# LEDs.net
KiCad netlist of a schematic drawn in Altium Designer
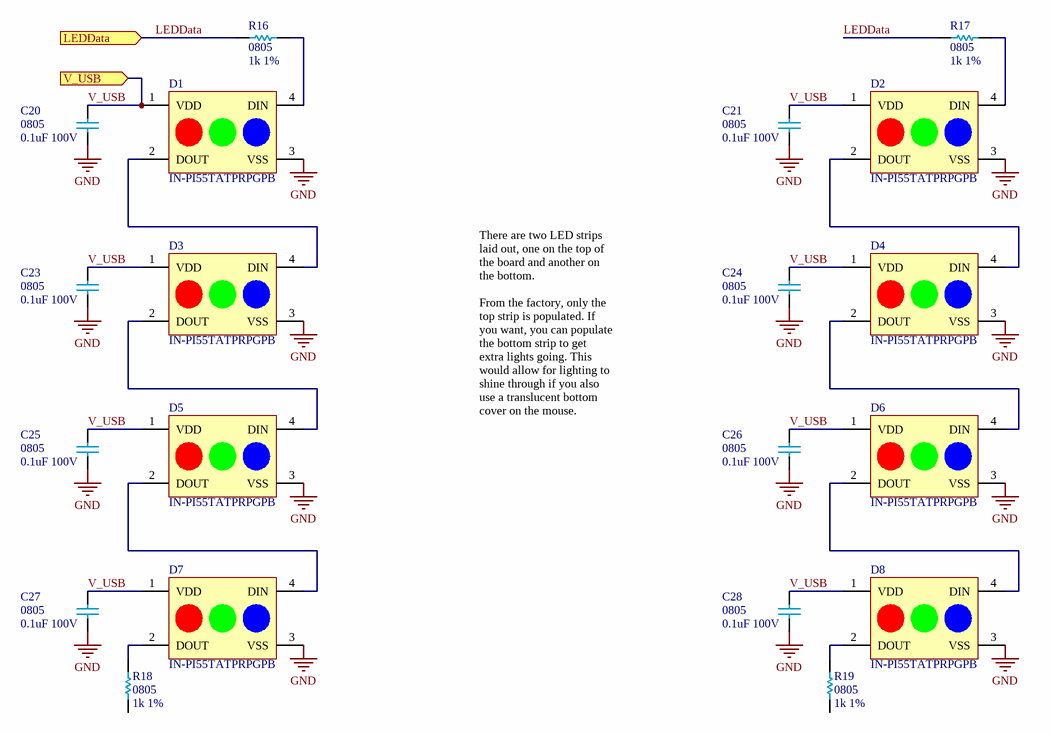
[diagram p0: LEDs.SchDoc]

(export (version "E")
  (design (tool "Eeschema 10.0.6"))
  (components
    (comp (ref "C20")
      (value "0805")
      (footprint "0805")
      (description "0805, X5R or better")
      (fields (field (name "ALTIUM_VALUE") "0.1uF 100V"))
      (libsource (lib "Chip_Passives") (part "Cap 0.1uF 100V"))
    )
    (comp (ref "C21")
      (value "0805")
      (footprint "0805")
      (description "0805, X5R or better")
      (fields (field (name "ALTIUM_VALUE") "0.1uF 100V"))
      (libsource (lib "Chip_Passives") (part "Cap 0.1uF 100V"))
    )
    (comp (ref "C23")
      (value "0805")
      (footprint "0805")
      (description "0805, X5R or better")
      (fields (field (name "ALTIUM_VALUE") "0.1uF 100V"))
      (libsource (lib "Chip_Passives") (part "Cap 0.1uF 100V"))
    )
    (comp (ref "C24")
      (value "0805")
      (footprint "0805")
      (description "0805, X5R or better")
      (fields (field (name "ALTIUM_VALUE") "0.1uF 100V"))
      (libsource (lib "Chip_Passives") (part "Cap 0.1uF 100V"))
    )
    (comp (ref "C25")
      (value "0805")
      (footprint "0805")
      (description "0805, X5R or better")
      (fields (field (name "ALTIUM_VALUE") "0.1uF 100V"))
      (libsource (lib "Chip_Passives") (part "Cap 0.1uF 100V"))
    )
    (comp (ref "C26")
      (value "0805")
      (footprint "0805")
      (description "0805, X5R or better")
      (fields (field (name "ALTIUM_VALUE") "0.1uF 100V"))
      (libsource (lib "Chip_Passives") (part "Cap 0.1uF 100V"))
    )
    (comp (ref "C27")
      (value "0805")
      (footprint "0805")
      (description "0805, X5R or better")
      (fields (field (name "ALTIUM_VALUE") "0.1uF 100V"))
      (libsource (lib "Chip_Passives") (part "Cap 0.1uF 100V"))
    )
    (comp (ref "C28")
      (value "0805")
      (footprint "0805")
      (description "0805, X5R or better")
      (fields (field (name "ALTIUM_VALUE") "0.1uF 100V"))
      (libsource (lib "Chip_Passives") (part "Cap 0.1uF 100V"))
    )
    (comp (ref "D1")
      (value "IN-PI55TATPRPGPB")
      (footprint "IN-PI55TATPRPGPB")
      (description "ADDRESS LED DISCRETE SERIAL RGB")
      (libsource (lib "LEDs") (part "IN-PI55TATPRPGPB"))
    )
    (comp (ref "D2")
      (value "IN-PI55TATPRPGPB")
      (footprint "IN-PI55TATPRPGPB")
      (description "ADDRESS LED DISCRETE SERIAL RGB")
      (libsource (lib "LEDs") (part "IN-PI55TATPRPGPB"))
    )
    (comp (ref "D3")
      (value "IN-PI55TATPRPGPB")
      (footprint "IN-PI55TATPRPGPB")
      (description "ADDRESS LED DISCRETE SERIAL RGB")
      (libsource (lib "LEDs") (part "IN-PI55TATPRPGPB"))
    )
    (comp (ref "D4")
      (value "IN-PI55TATPRPGPB")
      (footprint "IN-PI55TATPRPGPB")
      (description "ADDRESS LED DISCRETE SERIAL RGB")
      (libsource (lib "LEDs") (part "IN-PI55TATPRPGPB"))
    )
    (comp (ref "D5")
      (value "IN-PI55TATPRPGPB")
      (footprint "IN-PI55TATPRPGPB")
      (description "ADDRESS LED DISCRETE SERIAL RGB")
      (libsource (lib "LEDs") (part "IN-PI55TATPRPGPB"))
    )
    (comp (ref "D6")
      (value "IN-PI55TATPRPGPB")
      (footprint "IN-PI55TATPRPGPB")
      (description "ADDRESS LED DISCRETE SERIAL RGB")
      (libsource (lib "LEDs") (part "IN-PI55TATPRPGPB"))
    )
    (comp (ref "D7")
      (value "IN-PI55TATPRPGPB")
      (footprint "IN-PI55TATPRPGPB")
      (description "ADDRESS LED DISCRETE SERIAL RGB")
      (libsource (lib "LEDs") (part "IN-PI55TATPRPGPB"))
    )
    (comp (ref "D8")
      (value "IN-PI55TATPRPGPB")
      (footprint "IN-PI55TATPRPGPB")
      (description "ADDRESS LED DISCRETE SERIAL RGB")
      (libsource (lib "LEDs") (part "IN-PI55TATPRPGPB"))
    )
    (comp (ref "R16")
      (value "0805")
      (footprint "0805")
      (description "Chip resistor, 1/8W 100PPM")
      (fields (field (name "ALTIUM_VALUE") "1k 1%"))
      (libsource (lib "Chip_Passives") (part "Res 1k 1% 0805"))
    )
    (comp (ref "R17")
      (value "0805")
      (footprint "0805")
      (description "Chip resistor, 1/8W 100PPM")
      (fields (field (name "ALTIUM_VALUE") "1k 1%"))
      (libsource (lib "Chip_Passives") (part "Res 1k 1% 0805"))
    )
    (comp (ref "R18")
      (value "0805")
      (footprint "0805")
      (description "Chip resistor, 1/8W 100PPM")
      (fields (field (name "ALTIUM_VALUE") "1k 1%"))
      (libsource (lib "Chip_Passives") (part "Res 1k 1% 0805"))
    )
    (comp (ref "R19")
      (value "0805")
      (footprint "0805")
      (description "Chip resistor, 1/8W 100PPM")
      (fields (field (name "ALTIUM_VALUE") "1k 1%"))
      (libsource (lib "Chip_Passives") (part "Res 1k 1% 0805"))
    )
  )
  (nets
    (net (code "1") (name "/LEDData") (class "Default")
      (node (ref "R16") (pin "2") (pinfunction "2_2") (pintype "passive"))
      (node (ref "R17") (pin "2") (pinfunction "2_2") (pintype "passive"))
    )
    (net (code "2") (name "/V_USB") (class "Default")
      (node (ref "C20") (pin "2") (pinfunction "2_2") (pintype "passive"))
      (node (ref "C21") (pin "2") (pinfunction "2_2") (pintype "passive"))
      (node (ref "C23") (pin "2") (pinfunction "2_2") (pintype "passive"))
      (node (ref "C24") (pin "2") (pinfunction "2_2") (pintype "passive"))
      (node (ref "C25") (pin "2") (pinfunction "2_2") (pintype "passive"))
      (node (ref "C26") (pin "2") (pinfunction "2_2") (pintype "passive"))
      (node (ref "C27") (pin "2") (pinfunction "2_2") (pintype "passive"))
      (node (ref "C28") (pin "2") (pinfunction "2_2") (pintype "passive"))
      (node (ref "D1") (pin "1") (pinfunction "VDD_1") (pintype "passive"))
      (node (ref "D2") (pin "1") (pinfunction "VDD_1") (pintype "passive"))
      (node (ref "D3") (pin "1") (pinfunction "VDD_1") (pintype "passive"))
      (node (ref "D4") (pin "1") (pinfunction "VDD_1") (pintype "passive"))
      (node (ref "D5") (pin "1") (pinfunction "VDD_1") (pintype "passive"))
      (node (ref "D6") (pin "1") (pinfunction "VDD_1") (pintype "passive"))
      (node (ref "D7") (pin "1") (pinfunction "VDD_1") (pintype "passive"))
      (node (ref "D8") (pin "1") (pinfunction "VDD_1") (pintype "passive"))
    )
    (net (code "3") (name "GND") (class "Default")
      (node (ref "C20") (pin "1") (pinfunction "1_1") (pintype "passive"))
      (node (ref "C21") (pin "1") (pinfunction "1_1") (pintype "passive"))
      (node (ref "C23") (pin "1") (pinfunction "1_1") (pintype "passive"))
      (node (ref "C24") (pin "1") (pinfunction "1_1") (pintype "passive"))
      (node (ref "C25") (pin "1") (pinfunction "1_1") (pintype "passive"))
      (node (ref "C26") (pin "1") (pinfunction "1_1") (pintype "passive"))
      (node (ref "C27") (pin "1") (pinfunction "1_1") (pintype "passive"))
      (node (ref "C28") (pin "1") (pinfunction "1_1") (pintype "passive"))
      (node (ref "D1") (pin "3") (pinfunction "VSS_3") (pintype "passive"))
      (node (ref "D2") (pin "3") (pinfunction "VSS_3") (pintype "passive"))
      (node (ref "D3") (pin "3") (pinfunction "VSS_3") (pintype "passive"))
      (node (ref "D4") (pin "3") (pinfunction "VSS_3") (pintype "passive"))
      (node (ref "D5") (pin "3") (pinfunction "VSS_3") (pintype "passive"))
      (node (ref "D6") (pin "3") (pinfunction "VSS_3") (pintype "passive"))
      (node (ref "D7") (pin "3") (pinfunction "VSS_3") (pintype "passive"))
      (node (ref "D8") (pin "3") (pinfunction "VSS_3") (pintype "passive"))
    )
    (net (code "4") (name "Net-(D1-DIN)") (class "Default")
      (node (ref "D1") (pin "4") (pinfunction "DIN_4") (pintype "passive"))
      (node (ref "R16") (pin "1") (pinfunction "1_1") (pintype "passive"))
    )
    (net (code "5") (name "Net-(D1-DOUT)") (class "Default")
      (node (ref "D1") (pin "2") (pinfunction "DOUT_2") (pintype "passive"))
      (node (ref "D3") (pin "4") (pinfunction "DIN_4") (pintype "passive"))
    )
    (net (code "6") (name "Net-(D2-DIN)") (class "Default")
      (node (ref "D2") (pin "4") (pinfunction "DIN_4") (pintype "passive"))
      (node (ref "R17") (pin "1") (pinfunction "1_1") (pintype "passive"))
    )
    (net (code "7") (name "Net-(D2-DOUT)") (class "Default")
      (node (ref "D2") (pin "2") (pinfunction "DOUT_2") (pintype "passive"))
      (node (ref "D4") (pin "4") (pinfunction "DIN_4") (pintype "passive"))
    )
    (net (code "8") (name "Net-(D3-DOUT)") (class "Default")
      (node (ref "D3") (pin "2") (pinfunction "DOUT_2") (pintype "passive"))
      (node (ref "D5") (pin "4") (pinfunction "DIN_4") (pintype "passive"))
    )
    (net (code "9") (name "Net-(D4-DOUT)") (class "Default")
      (node (ref "D4") (pin "2") (pinfunction "DOUT_2") (pintype "passive"))
      (node (ref "D6") (pin "4") (pinfunction "DIN_4") (pintype "passive"))
    )
    (net (code "10") (name "Net-(D5-DOUT)") (class "Default")
      (node (ref "D5") (pin "2") (pinfunction "DOUT_2") (pintype "passive"))
      (node (ref "D7") (pin "4") (pinfunction "DIN_4") (pintype "passive"))
    )
    (net (code "11") (name "Net-(D6-DOUT)") (class "Default")
      (node (ref "D6") (pin "2") (pinfunction "DOUT_2") (pintype "passive"))
      (node (ref "D8") (pin "4") (pinfunction "DIN_4") (pintype "passive"))
    )
    (net (code "12") (name "Net-(D7-DOUT)") (class "Default")
      (node (ref "D7") (pin "2") (pinfunction "DOUT_2") (pintype "passive"))
      (node (ref "R18") (pin "2") (pinfunction "2_2") (pintype "passive"))
    )
    (net (code "13") (name "Net-(D8-DOUT)") (class "Default")
      (node (ref "D8") (pin "2") (pinfunction "DOUT_2") (pintype "passive"))
      (node (ref "R19") (pin "2") (pinfunction "2_2") (pintype "passive"))
    )
    (net (code "14") (name "unconnected-(R18-Pad1)") (class "Default")
      (node (ref "R18") (pin "1") (pinfunction "1_1") (pintype "passive"))
    )
    (net (code "15") (name "unconnected-(R19-Pad1)") (class "Default")
      (node (ref "R19") (pin "1") (pinfunction "1_1") (pintype "passive"))
    )
  )
)
